# chess_module_HEF.net
KiCad netlist of a schematic drawn in Altium Designer
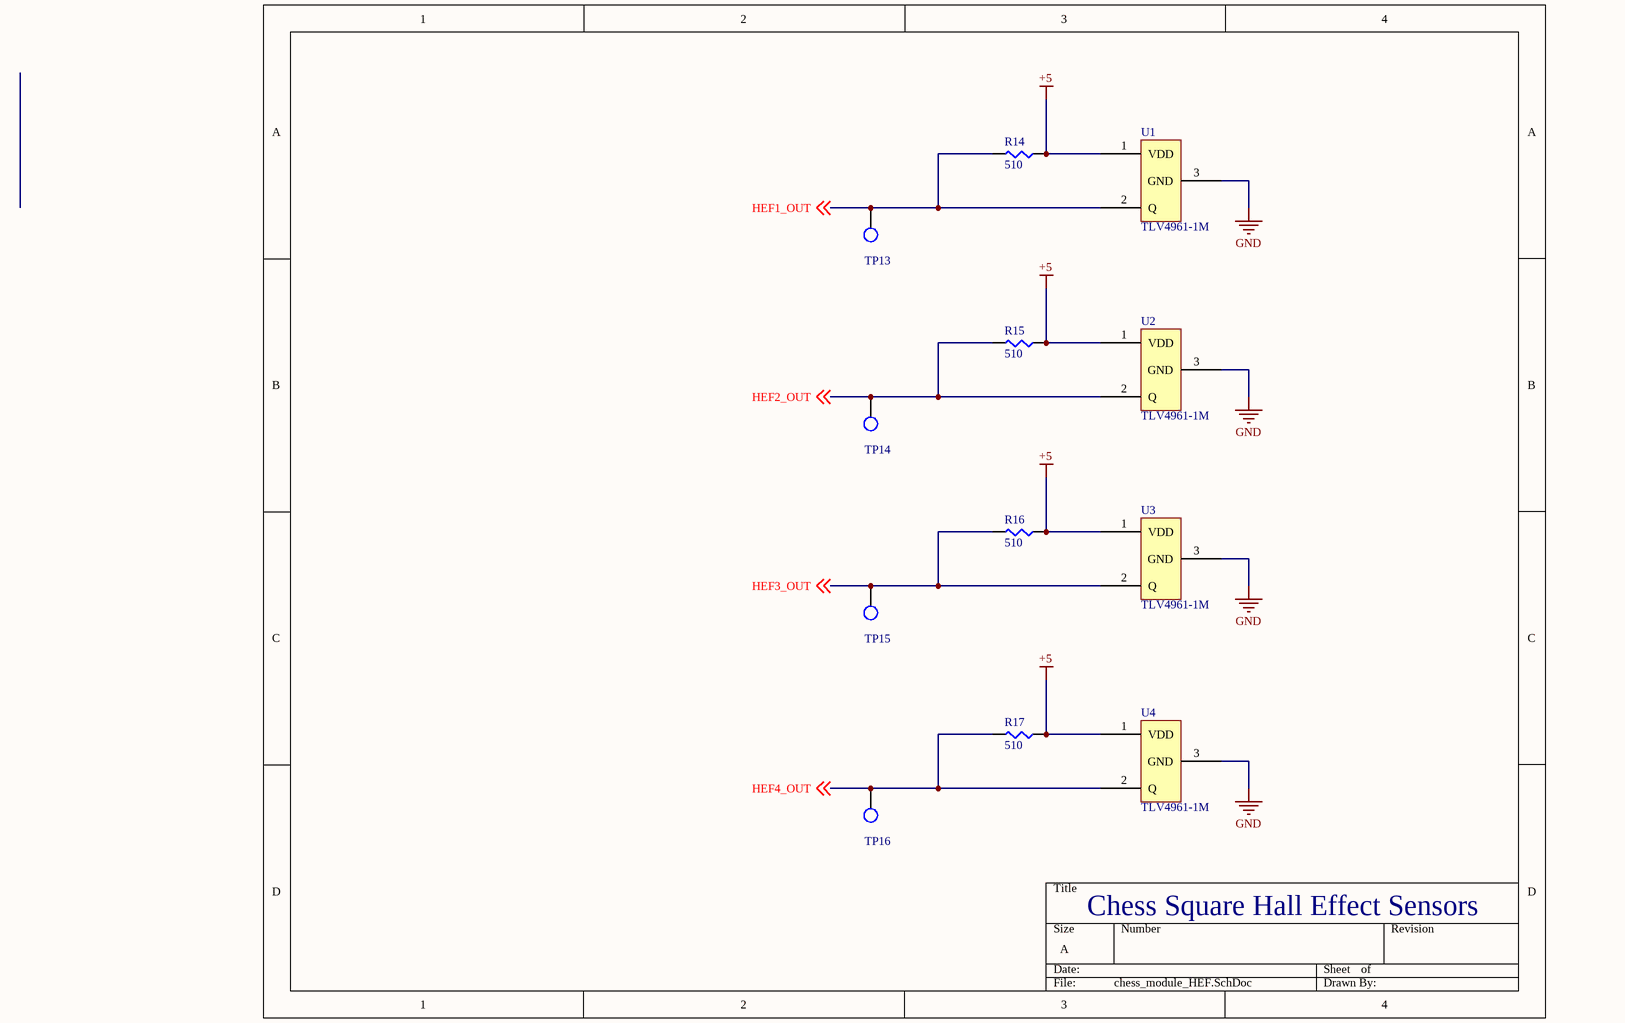
[diagram p0: chess_module_HEF.SchDoc]

(export (version "E")
  (design (tool "Eeschema 10.0.6"))
  (components
    (comp (ref "R14")
      (value "510")
      (footprint "SMD-0805-RES")
      (description "RES SMD 510 OHM 1% 1/8W 0805")
      (fields (field (name "PART NUMBER") "ERJ-6ENF5100V") (field (name "DIGI-KEY PART NUMBER") "P510CCT-ND"))
      (libsource (lib "chess_module") (part "ERJ-6ENF5100V"))
    )
    (comp (ref "R15")
      (value "510")
      (footprint "SMD-0805-RES")
      (description "RES SMD 510 OHM 1% 1/8W 0805")
      (fields (field (name "PART NUMBER") "ERJ-6ENF5100V") (field (name "DIGI-KEY PART NUMBER") "P510CCT-ND"))
      (libsource (lib "chess_module") (part "ERJ-6ENF5100V"))
    )
    (comp (ref "R16")
      (value "510")
      (footprint "SMD-0805-RES")
      (description "RES SMD 510 OHM 1% 1/8W 0805")
      (fields (field (name "PART NUMBER") "ERJ-6ENF5100V") (field (name "DIGI-KEY PART NUMBER") "P510CCT-ND"))
      (libsource (lib "chess_module") (part "ERJ-6ENF5100V"))
    )
    (comp (ref "R17")
      (value "510")
      (footprint "SMD-0805-RES")
      (description "RES SMD 510 OHM 1% 1/8W 0805")
      (fields (field (name "PART NUMBER") "ERJ-6ENF5100V") (field (name "DIGI-KEY PART NUMBER") "P510CCT-ND"))
      (libsource (lib "chess_module") (part "ERJ-6ENF5100V"))
    )
    (comp (ref "TP13")
      (value "TP_1206")
      (footprint "TP-SMC-1206")
      (description "Test Point SMD 1206")
      (fields
        (field (name "MANUFACTURER") "TE Connectivity (Tyco Electronics)")
        (field (name "MANUFACTURER PART NUMBER") "1625854-1")
      )
      (libsource (lib "base-board") (part "TP_1206"))
    )
    (comp (ref "TP14")
      (value "TP_1206")
      (footprint "TP-SMC-1206")
      (description "Test Point SMD 1206")
      (fields
        (field (name "MANUFACTURER") "TE Connectivity (Tyco Electronics)")
        (field (name "MANUFACTURER PART NUMBER") "1625854-1")
      )
      (libsource (lib "base-board") (part "TP_1206"))
    )
    (comp (ref "TP15")
      (value "TP_1206")
      (footprint "TP-SMC-1206")
      (description "Test Point SMD 1206")
      (fields
        (field (name "MANUFACTURER") "TE Connectivity (Tyco Electronics)")
        (field (name "MANUFACTURER PART NUMBER") "1625854-1")
      )
      (libsource (lib "base-board") (part "TP_1206"))
    )
    (comp (ref "TP16")
      (value "TP_1206")
      (footprint "TP-SMC-1206")
      (description "Test Point SMD 1206")
      (fields
        (field (name "MANUFACTURER") "TE Connectivity (Tyco Electronics)")
        (field (name "MANUFACTURER PART NUMBER") "1625854-1")
      )
      (libsource (lib "base-board") (part "TP_1206"))
    )
    (comp (ref "U1")
      (value "TLV4961-1M")
      (footprint "SOT95P245X110-3N")
      (description "Hall Effect Sensor")
      (libsource (lib "chess_module") (part "TLV4961-1M"))
    )
    (comp (ref "U2")
      (value "TLV4961-1M")
      (footprint "SOT95P245X110-3N")
      (description "Hall Effect Sensor")
      (libsource (lib "chess_module") (part "TLV4961-1M"))
    )
    (comp (ref "U3")
      (value "TLV4961-1M")
      (footprint "SOT95P245X110-3N")
      (description "Hall Effect Sensor")
      (libsource (lib "chess_module") (part "TLV4961-1M"))
    )
    (comp (ref "U4")
      (value "TLV4961-1M")
      (footprint "SOT95P245X110-3N")
      (description "Hall Effect Sensor")
      (libsource (lib "chess_module") (part "TLV4961-1M"))
    )
  )
  (nets
    (net (code "1") (name "+5") (class "Default")
      (node (ref "R14") (pin "1") (pinfunction "1_1") (pintype "passive"))
      (node (ref "R15") (pin "1") (pinfunction "1_1") (pintype "passive"))
      (node (ref "R16") (pin "1") (pinfunction "1_1") (pintype "passive"))
      (node (ref "R17") (pin "1") (pinfunction "1_1") (pintype "passive"))
      (node (ref "U1") (pin "1") (pinfunction "VDD_1") (pintype "passive"))
      (node (ref "U2") (pin "1") (pinfunction "VDD_1") (pintype "passive"))
      (node (ref "U3") (pin "1") (pinfunction "VDD_1") (pintype "passive"))
      (node (ref "U4") (pin "1") (pinfunction "VDD_1") (pintype "passive"))
    )
    (net (code "2") (name "GND") (class "Default")
      (node (ref "U1") (pin "3") (pinfunction "GND_3") (pintype "passive"))
      (node (ref "U2") (pin "3") (pinfunction "GND_3") (pintype "passive"))
      (node (ref "U3") (pin "3") (pinfunction "GND_3") (pintype "passive"))
      (node (ref "U4") (pin "3") (pinfunction "GND_3") (pintype "passive"))
    )
    (net (code "3") (name "HEF1_OUT") (class "Default")
      (node (ref "R14") (pin "2") (pinfunction "2_2") (pintype "passive"))
      (node (ref "TP13") (pin "1") (pintype "passive"))
      (node (ref "U1") (pin "2") (pinfunction "Q_2") (pintype "passive"))
    )
    (net (code "4") (name "HEF2_OUT") (class "Default")
      (node (ref "R15") (pin "2") (pinfunction "2_2") (pintype "passive"))
      (node (ref "TP14") (pin "1") (pintype "passive"))
      (node (ref "U2") (pin "2") (pinfunction "Q_2") (pintype "passive"))
    )
    (net (code "5") (name "HEF3_OUT") (class "Default")
      (node (ref "R16") (pin "2") (pinfunction "2_2") (pintype "passive"))
      (node (ref "TP15") (pin "1") (pintype "passive"))
      (node (ref "U3") (pin "2") (pinfunction "Q_2") (pintype "passive"))
    )
    (net (code "6") (name "HEF4_OUT") (class "Default")
      (node (ref "R17") (pin "2") (pinfunction "2_2") (pintype "passive"))
      (node (ref "TP16") (pin "1") (pintype "passive"))
      (node (ref "U4") (pin "2") (pinfunction "Q_2") (pintype "passive"))
    )
  )
)
